# CLAMPER_SCHEMATIC.net
KiCad netlist of a schematic drawn in EasyEDA
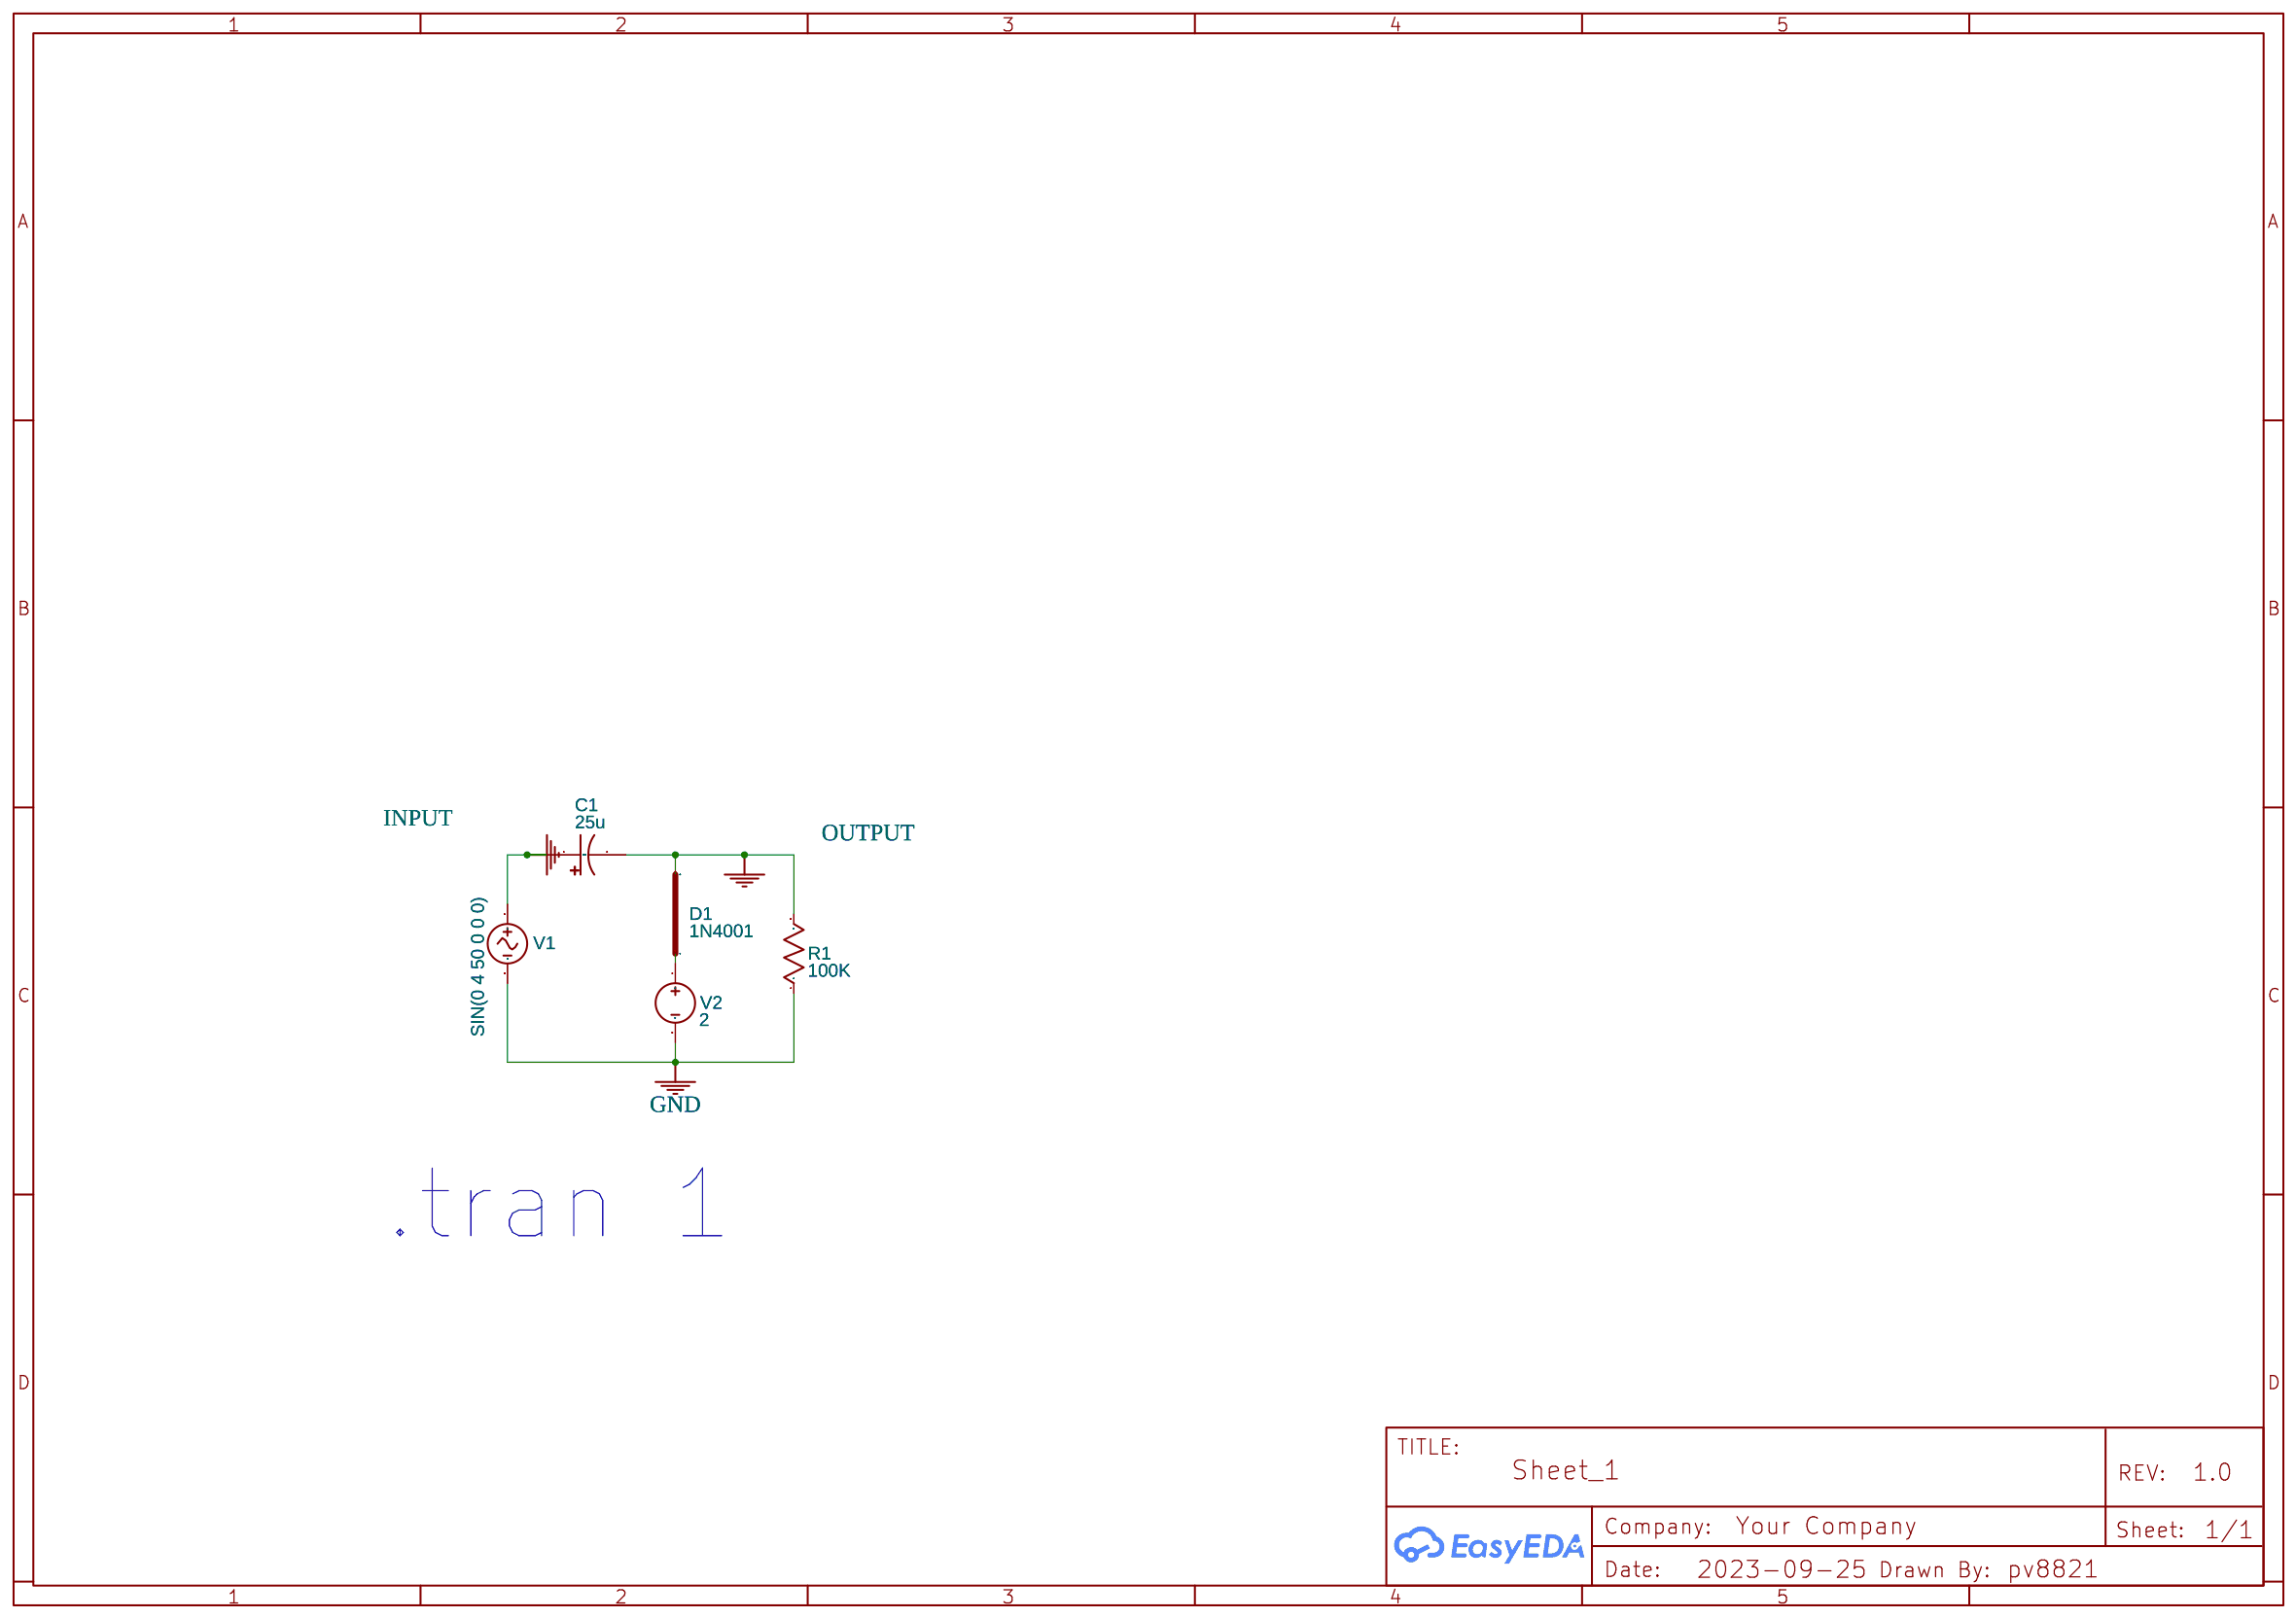
[diagram p0: schematic sheet]

(export (version "E")
  (design (tool "Eeschema 10.0.6"))
  (components
    (comp (ref "C1") (value "25u") (libsource (lib "") (part "Capacitor_Electrolytic_US")))
    (comp (ref "D1") (value "1N4001") (libsource (lib "") (part "1N4001")))
    (comp (ref "R1") (value "100K") (libsource (lib "") (part "Resistor_US")))
    (comp (ref "V1") (value "SIN(0 4 50 0 0 0)") (libsource (lib "") (part "VSin")))
    (comp (ref "V2") (value "2") (libsource (lib "") (part "VDC")))
  )
  (nets
    (net (code "1") (name "GND") (class "Default")
      (node (ref "R1") (pin "1") (pinfunction "1_1") (pintype "unspecified"))
      (node (ref "V1") (pin "2") (pinfunction "2_2") (pintype "unspecified"))
      (node (ref "V2") (pin "2") (pinfunction "2_2") (pintype "unspecified"))
    )
    (net (code "2") (name "INPUT") (class "Default")
      (node (ref "C1") (pin "1") (pinfunction "1_1") (pintype "unspecified"))
      (node (ref "V1") (pin "1") (pinfunction "1_1") (pintype "unspecified"))
    )
    (net (code "3") (name "Net-(D1-Pad1)") (class "Default")
      (node (ref "D1") (pin "1") (pinfunction "1_1") (pintype "unspecified"))
      (node (ref "V2") (pin "1") (pinfunction "1_1") (pintype "unspecified"))
    )
    (net (code "4") (name "OUTPUT") (class "Default")
      (node (ref "C1") (pin "2") (pinfunction "2_2") (pintype "unspecified"))
      (node (ref "D1") (pin "2") (pinfunction "2_2") (pintype "unspecified"))
      (node (ref "R1") (pin "2") (pinfunction "2_2") (pintype "unspecified"))
    )
  )
)
